# ftdi.net
KiCad netlist of a schematic drawn in EAGLE
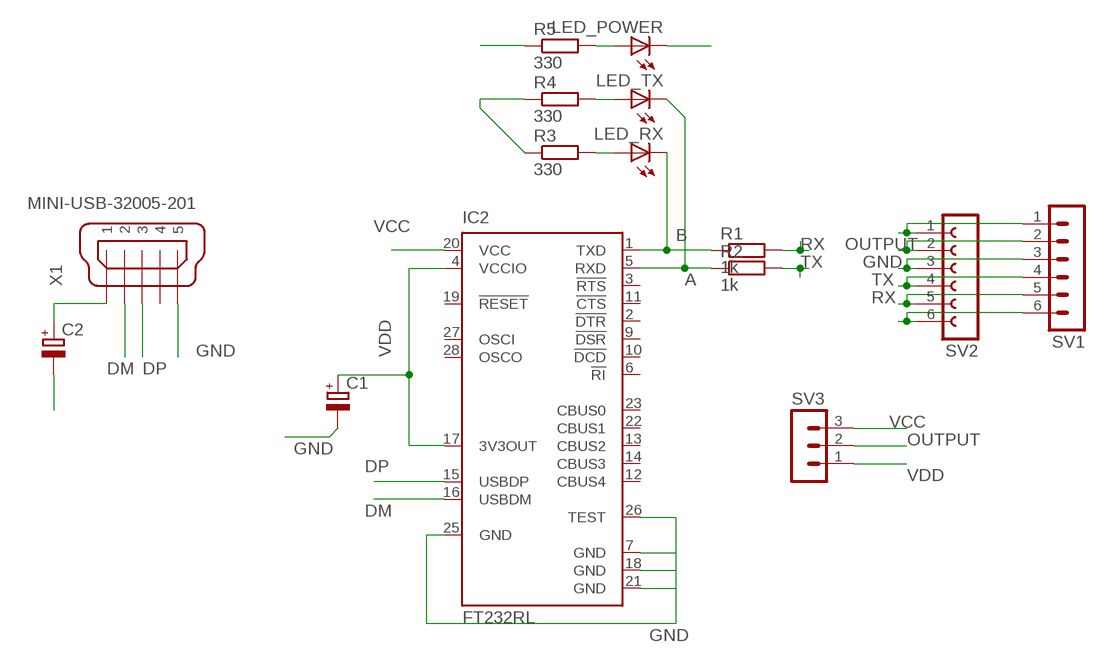
[diagram p0: schematic, sheet 1]

(export (version "E")
  (design (tool "Eeschema 10.0.6"))
  (components
    (comp (ref "C1")
      (value "CPOL-EUE2.5-5")
      (footprint "eagle-import:E2,5-5")
      (libsource (lib "eagle-import") (part "CPOL-EUE2.5-5"))
    )
    (comp (ref "C2")
      (value "CPOL-EUE2.5-5")
      (footprint "eagle-import:E2,5-5")
      (libsource (lib "eagle-import") (part "CPOL-EUE2.5-5"))
    )
    (comp (ref "IC2")
      (value "FT232RL")
      (footprint "eagle-import:SSOP28")
      (libsource (lib "eagle-import") (part "FT232RL"))
    )
    (comp (ref "LED_POWER")
      (value "LED3MM")
      (footprint "eagle-import:LED3MM")
      (libsource (lib "eagle-import") (part "LED3MM"))
    )
    (comp (ref "LED_RX")
      (value "LED3MM")
      (footprint "eagle-import:LED3MM")
      (libsource (lib "eagle-import") (part "LED3MM"))
    )
    (comp (ref "LED_TX")
      (value "LED3MM")
      (footprint "eagle-import:LED3MM")
      (libsource (lib "eagle-import") (part "LED3MM"))
    )
    (comp (ref "R1")
      (value "1k")
      (footprint "eagle-import:0204_7")
      (libsource (lib "eagle-import") (part "R-EU_0204/7"))
    )
    (comp (ref "R2")
      (value "1k")
      (footprint "eagle-import:0204_7")
      (libsource (lib "eagle-import") (part "R-EU_0204/7"))
    )
    (comp (ref "R3")
      (value "330")
      (footprint "eagle-import:0204_7")
      (libsource (lib "eagle-import") (part "R-EU_0204/7"))
    )
    (comp (ref "R4")
      (value "330")
      (footprint "eagle-import:0204_7")
      (libsource (lib "eagle-import") (part "R-EU_0204/7"))
    )
    (comp (ref "R5")
      (value "330")
      (footprint "eagle-import:0204_7")
      (libsource (lib "eagle-import") (part "R-EU_0204/7"))
    )
    (comp (ref "SV1")
      (value "MA06-1")
      (footprint "eagle-import:MA06-1")
      (libsource (lib "eagle-import") (part "MA06-1"))
    )
    (comp (ref "SV2")
      (value "FE06-1")
      (footprint "eagle-import:FE06")
      (libsource (lib "eagle-import") (part "FE06-1"))
    )
    (comp (ref "SV3")
      (value "MA03-1")
      (footprint "eagle-import:MA03-1")
      (libsource (lib "eagle-import") (part "MA03-1"))
    )
    (comp (ref "X1")
      (value "MINI-USB-32005-201")
      (footprint "eagle-import:32005-201")
      (libsource (lib "eagle-import") (part "MINI-USB-32005-201"))
    )
  )
  (nets
    (net (code "1") (name "/A") (class "Default")
      (node (ref "IC2") (pin "5") (pinfunction "RXD_5") (pintype "input"))
      (node (ref "LED_TX") (pin "K") (pinfunction "C_K") (pintype "passive"))
      (node (ref "R2") (pin "1") (pinfunction "1_1") (pintype "passive"))
    )
    (net (code "2") (name "/B") (class "Default")
      (node (ref "IC2") (pin "1") (pinfunction "TXD_1") (pintype "output"))
      (node (ref "LED_RX") (pin "K") (pinfunction "C_K") (pintype "passive"))
      (node (ref "R1") (pin "1") (pinfunction "1_1") (pintype "passive"))
    )
    (net (code "3") (name "/DM") (class "Default")
      (node (ref "IC2") (pin "16") (pinfunction "USBDM_16") (pintype "bidirectional"))
      (node (ref "X1") (pin "2") (pinfunction "2_2") (pintype "passive"))
    )
    (net (code "4") (name "/DP") (class "Default")
      (node (ref "IC2") (pin "15") (pinfunction "USBDP_15") (pintype "bidirectional"))
      (node (ref "X1") (pin "3") (pinfunction "3_3") (pintype "passive"))
    )
    (net (code "5") (name "/GND") (class "Default")
      (node (ref "C1") (pin "-") (pinfunction "-_-") (pintype "passive"))
      (node (ref "C2") (pin "-") (pinfunction "-_-") (pintype "passive"))
      (node (ref "IC2") (pin "18") (pinfunction "GND_18") (pintype "power_in"))
      (node (ref "IC2") (pin "21") (pinfunction "GND_21") (pintype "power_in"))
      (node (ref "IC2") (pin "25") (pinfunction "GND_25") (pintype "power_in"))
      (node (ref "IC2") (pin "26") (pinfunction "TEST_26") (pintype "input"))
      (node (ref "IC2") (pin "7") (pinfunction "GND_7") (pintype "power_in"))
      (node (ref "LED_POWER") (pin "K") (pinfunction "C_K") (pintype "passive"))
      (node (ref "SV1") (pin "3") (pinfunction "3_3") (pintype "passive"))
      (node (ref "SV2") (pin "3") (pinfunction "3_3") (pintype "passive"))
      (node (ref "X1") (pin "5") (pinfunction "5_5") (pintype "passive"))
    )
    (net (code "6") (name "/OUTPUT") (class "Default")
      (node (ref "SV1") (pin "2") (pinfunction "2_2") (pintype "passive"))
      (node (ref "SV2") (pin "2") (pinfunction "2_2") (pintype "passive"))
      (node (ref "SV3") (pin "2") (pinfunction "2_2") (pintype "passive"))
    )
    (net (code "7") (name "/RX") (class "Default")
      (node (ref "R1") (pin "2") (pinfunction "2_2") (pintype "passive"))
      (node (ref "SV1") (pin "5") (pinfunction "5_5") (pintype "passive"))
      (node (ref "SV2") (pin "5") (pinfunction "5_5") (pintype "passive"))
    )
    (net (code "8") (name "/TX") (class "Default")
      (node (ref "R2") (pin "2") (pinfunction "2_2") (pintype "passive"))
      (node (ref "SV1") (pin "4") (pinfunction "4_4") (pintype "passive"))
      (node (ref "SV2") (pin "4") (pinfunction "4_4") (pintype "passive"))
    )
    (net (code "9") (name "/VCC") (class "Default")
      (node (ref "C2") (pin "+") (pinfunction "+_+") (pintype "passive"))
      (node (ref "IC2") (pin "20") (pinfunction "VCC_20") (pintype "power_in"))
      (node (ref "R5") (pin "1") (pinfunction "1_1") (pintype "passive"))
      (node (ref "SV3") (pin "3") (pinfunction "3_3") (pintype "passive"))
      (node (ref "X1") (pin "1") (pinfunction "1_1") (pintype "passive"))
    )
    (net (code "10") (name "/VDD") (class "Default")
      (node (ref "C1") (pin "+") (pinfunction "+_+") (pintype "passive"))
      (node (ref "IC2") (pin "17") (pinfunction "3V3OUT_17") (pintype "output"))
      (node (ref "IC2") (pin "4") (pinfunction "VCCIO_4") (pintype "power_in"))
      (node (ref "R3") (pin "1") (pinfunction "1_1") (pintype "passive"))
      (node (ref "R4") (pin "1") (pinfunction "1_1") (pintype "passive"))
      (node (ref "SV3") (pin "1") (pinfunction "1_1") (pintype "passive"))
    )
    (net (code "11") (name "Net-(LED_POWER-PadA)") (class "Default")
      (node (ref "LED_POWER") (pin "A") (pinfunction "A_A") (pintype "passive"))
      (node (ref "R5") (pin "2") (pinfunction "2_2") (pintype "passive"))
    )
    (net (code "12") (name "Net-(LED_RX-PadA)") (class "Default")
      (node (ref "LED_RX") (pin "A") (pinfunction "A_A") (pintype "passive"))
      (node (ref "R3") (pin "2") (pinfunction "2_2") (pintype "passive"))
    )
    (net (code "13") (name "Net-(LED_TX-PadA)") (class "Default")
      (node (ref "LED_TX") (pin "A") (pinfunction "A_A") (pintype "passive"))
      (node (ref "R4") (pin "2") (pinfunction "2_2") (pintype "passive"))
    )
    (net (code "14") (name "Net-(SV1-Pad1)") (class "Default")
      (node (ref "SV1") (pin "1") (pinfunction "1_1") (pintype "passive"))
      (node (ref "SV2") (pin "1") (pinfunction "1_1") (pintype "passive"))
    )
    (net (code "15") (name "Net-(SV1-Pad6)") (class "Default")
      (node (ref "SV1") (pin "6") (pinfunction "6_6") (pintype "passive"))
      (node (ref "SV2") (pin "6") (pinfunction "6_6") (pintype "passive"))
    )
    (net (code "16") (name "unconnected-(IC2-CBUS0-Pad23)") (class "Default")
      (node (ref "IC2") (pin "23") (pinfunction "CBUS0_23") (pintype "bidirectional"))
    )
    (net (code "17") (name "unconnected-(IC2-CBUS1-Pad22)") (class "Default")
      (node (ref "IC2") (pin "22") (pinfunction "CBUS1_22") (pintype "bidirectional"))
    )
    (net (code "18") (name "unconnected-(IC2-CBUS2-Pad13)") (class "Default")
      (node (ref "IC2") (pin "13") (pinfunction "CBUS2_13") (pintype "bidirectional"))
    )
    (net (code "19") (name "unconnected-(IC2-CBUS3-Pad14)") (class "Default")
      (node (ref "IC2") (pin "14") (pinfunction "CBUS3_14") (pintype "bidirectional"))
    )
    (net (code "20") (name "unconnected-(IC2-CBUS4-Pad12)") (class "Default")
      (node (ref "IC2") (pin "12") (pinfunction "CBUS4_12") (pintype "bidirectional"))
    )
    (net (code "21") (name "unconnected-(IC2-OSCI-Pad27)") (class "Default")
      (node (ref "IC2") (pin "27") (pinfunction "OSCI_27") (pintype "input"))
    )
    (net (code "22") (name "unconnected-(IC2-OSCO-Pad28)") (class "Default")
      (node (ref "IC2") (pin "28") (pinfunction "OSCO_28") (pintype "output"))
    )
    (net (code "23") (name "unconnected-(IC2-~{CTS}-Pad11)") (class "Default")
      (node (ref "IC2") (pin "11") (pinfunction "~{CTS}_11") (pintype "input"))
    )
    (net (code "24") (name "unconnected-(IC2-~{DCD}-Pad10)") (class "Default")
      (node (ref "IC2") (pin "10") (pinfunction "~{DCD}_10") (pintype "input"))
    )
    (net (code "25") (name "unconnected-(IC2-~{DSR}-Pad9)") (class "Default")
      (node (ref "IC2") (pin "9") (pinfunction "~{DSR}_9") (pintype "input"))
    )
    (net (code "26") (name "unconnected-(IC2-~{DTR}-Pad2)") (class "Default")
      (node (ref "IC2") (pin "2") (pinfunction "~{DTR}_2") (pintype "output"))
    )
    (net (code "27") (name "unconnected-(IC2-~{RESET}-Pad19)") (class "Default")
      (node (ref "IC2") (pin "19") (pinfunction "~{RESET}_19") (pintype "input"))
    )
    (net (code "28") (name "unconnected-(IC2-~{RI}-Pad6)") (class "Default")
      (node (ref "IC2") (pin "6") (pinfunction "~{RI}_6") (pintype "input"))
    )
    (net (code "29") (name "unconnected-(IC2-~{RTS}-Pad3)") (class "Default")
      (node (ref "IC2") (pin "3") (pinfunction "~{RTS}_3") (pintype "output"))
    )
    (net (code "30") (name "unconnected-(X1-Pad4)") (class "Default")
      (node (ref "X1") (pin "4") (pinfunction "4_4") (pintype "passive"))
    )
  )
)
